# zx81_SD_09.net
KiCad netlist of a schematic drawn in EAGLE
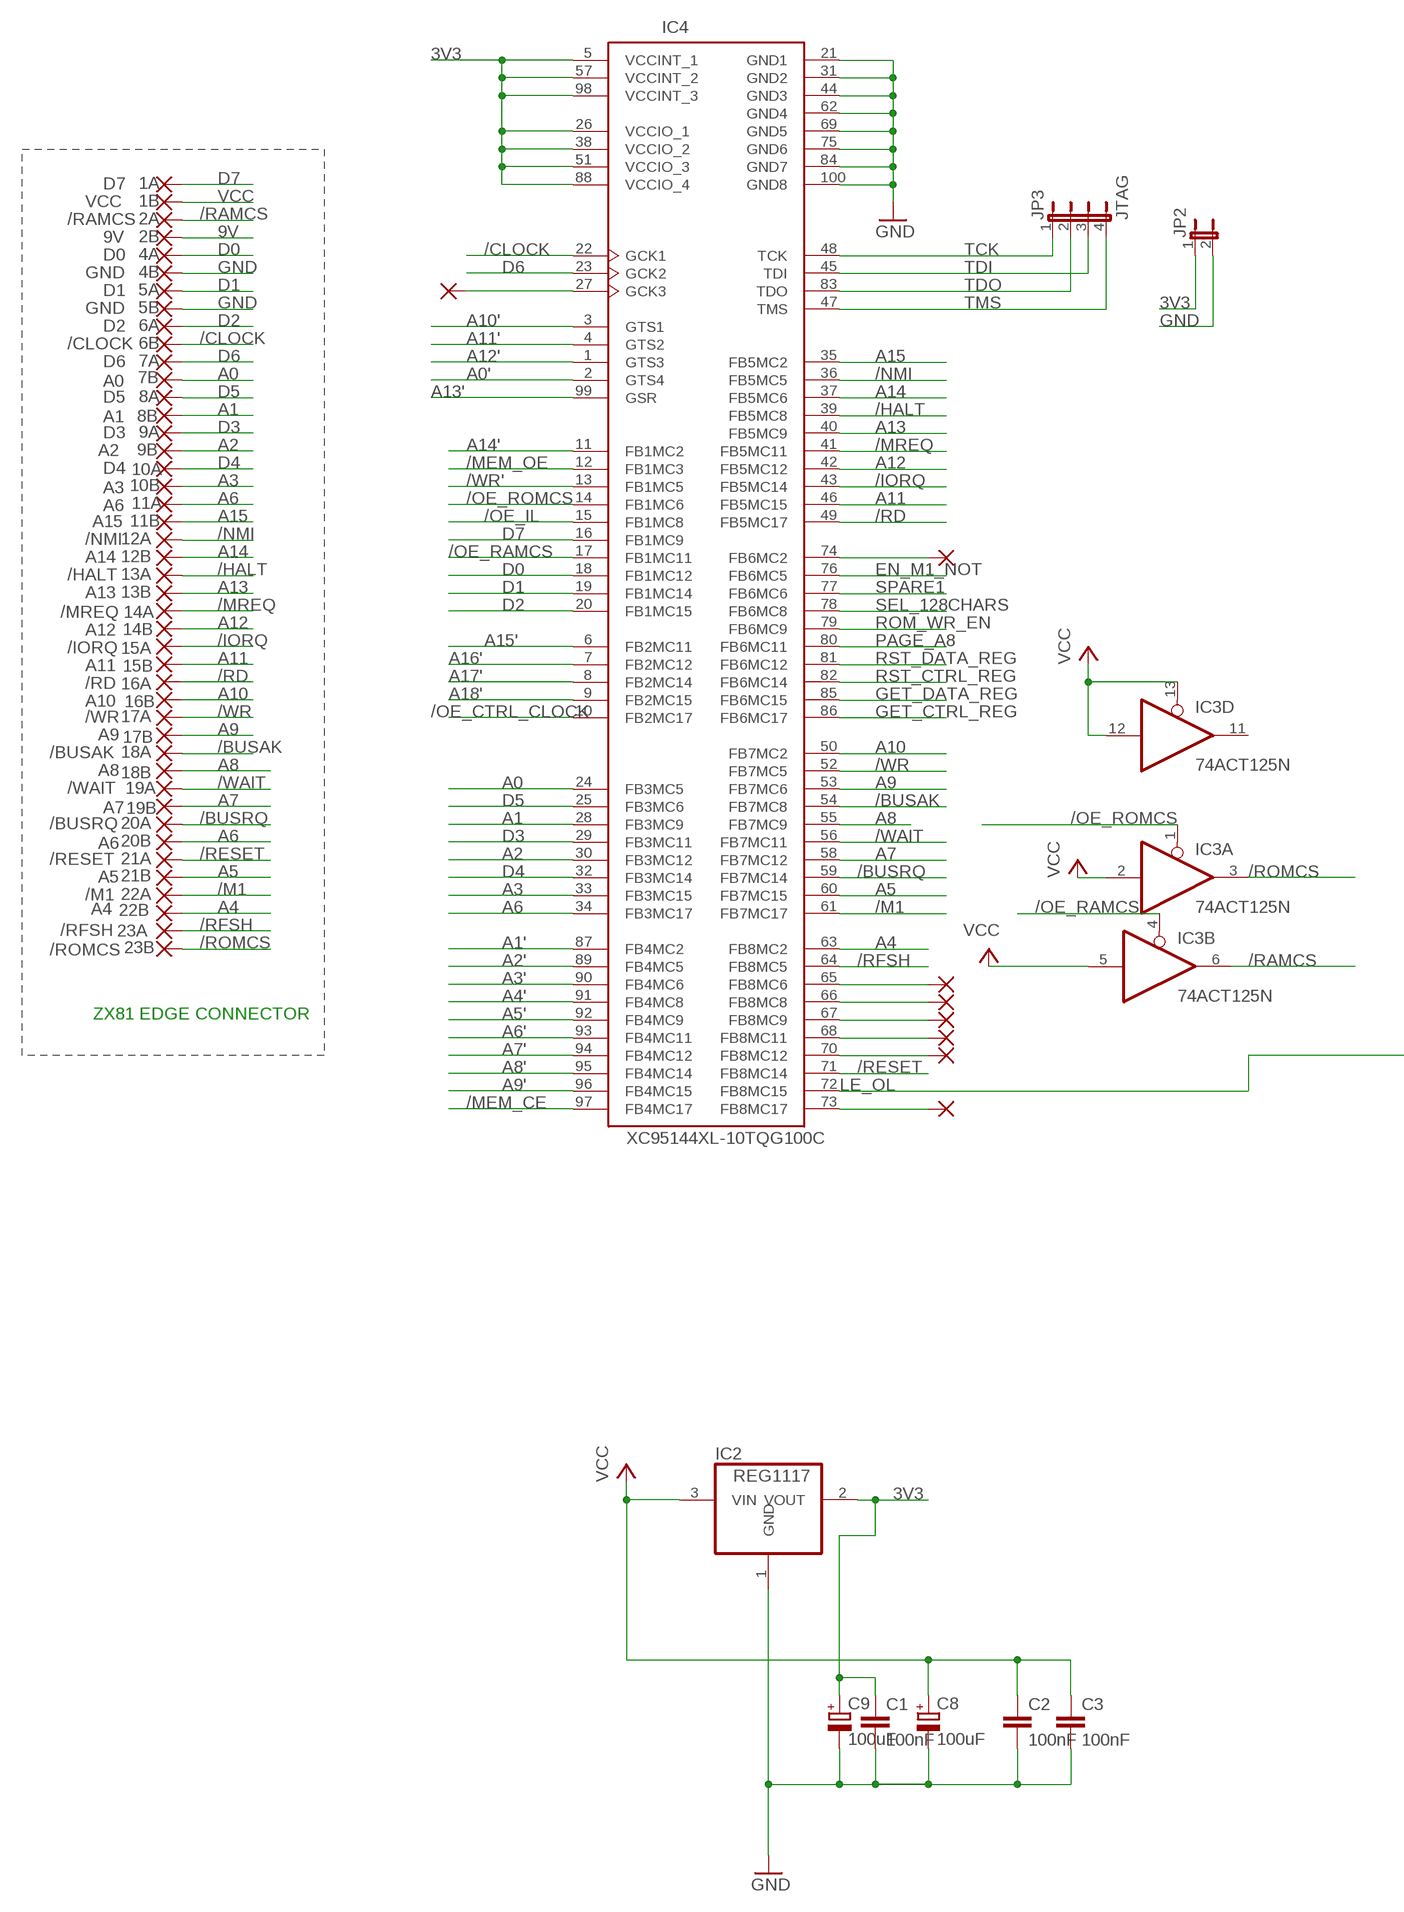
[diagram p0: schematic, sheet 1, part 1 of 2]
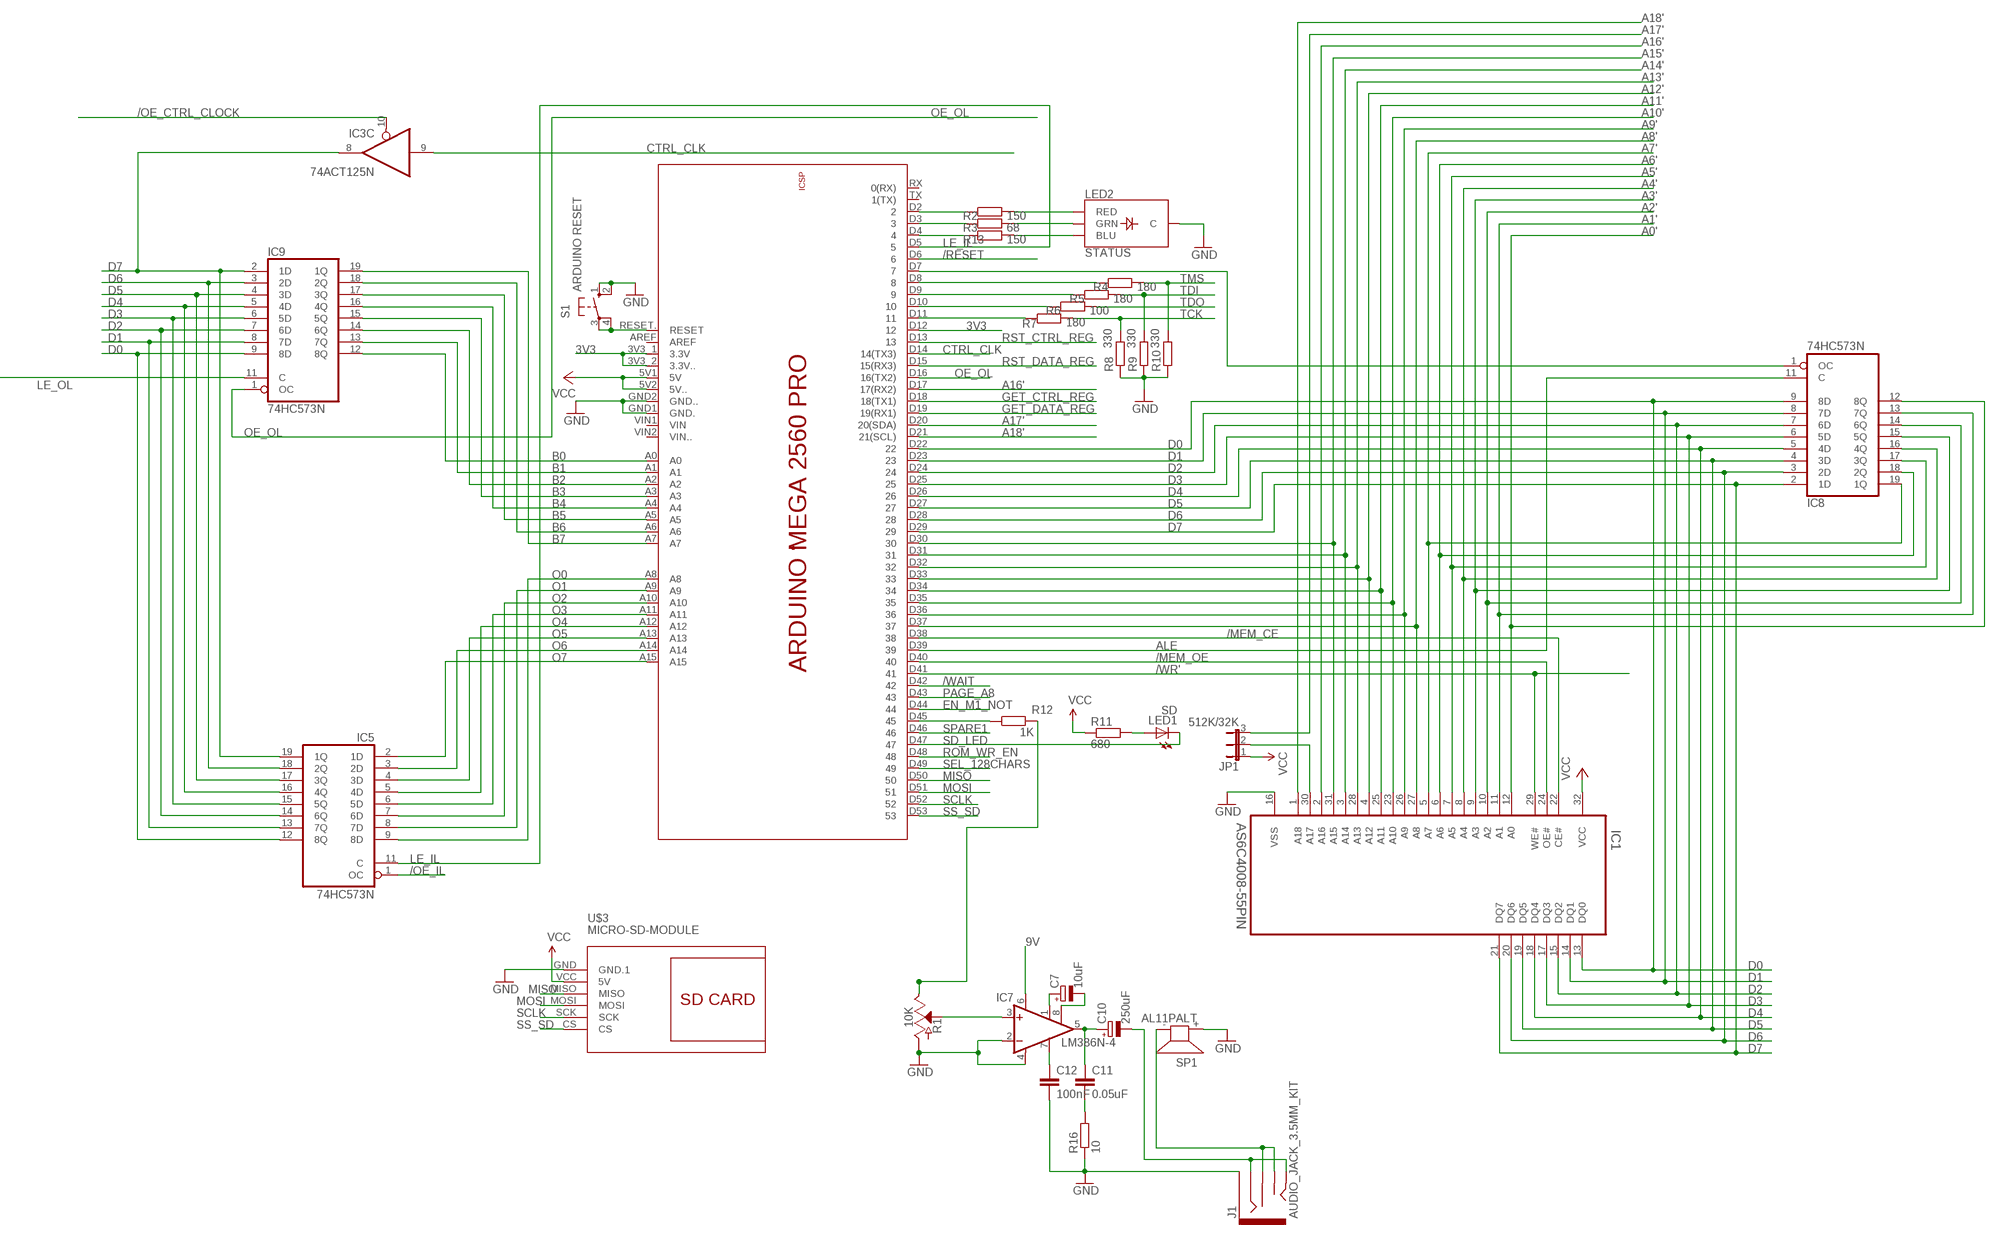
[diagram p1: schematic, sheet 1, part 2 of 2]

(export (version "E")
  (design (tool "Eeschema 10.0.6"))
  (components
    (comp (ref "1A")
      (value "D7")
      (footprint "eagle-import:EDGEPIN")
      (libsource (lib "eagle-import") (part "SMD2EDGEPIN"))
    )
    (comp (ref "1B")
      (value "VCC")
      (footprint "eagle-import:EDGEPIN")
      (libsource (lib "eagle-import") (part "SMD2EDGEPIN"))
    )
    (comp (ref "2A")
      (value "/RAMCS")
      (footprint "eagle-import:EDGEPIN")
      (libsource (lib "eagle-import") (part "SMD2EDGEPIN"))
    )
    (comp (ref "2B")
      (value "9V")
      (footprint "eagle-import:EDGEPIN")
      (libsource (lib "eagle-import") (part "SMD2EDGEPIN"))
    )
    (comp (ref "4A")
      (value "D0")
      (footprint "eagle-import:EDGEPIN")
      (libsource (lib "eagle-import") (part "SMD2EDGEPIN"))
    )
    (comp (ref "4B")
      (value "GND")
      (footprint "eagle-import:EDGEPIN")
      (libsource (lib "eagle-import") (part "SMD2EDGEPIN"))
    )
    (comp (ref "5A")
      (value "D1")
      (footprint "eagle-import:EDGEPIN")
      (libsource (lib "eagle-import") (part "SMD2EDGEPIN"))
    )
    (comp (ref "5B")
      (value "GND")
      (footprint "eagle-import:EDGEPIN")
      (libsource (lib "eagle-import") (part "SMD2EDGEPIN"))
    )
    (comp (ref "6A")
      (value "D2")
      (footprint "eagle-import:EDGEPIN")
      (libsource (lib "eagle-import") (part "SMD2EDGEPIN"))
    )
    (comp (ref "6B")
      (value "/CLOCK")
      (footprint "eagle-import:EDGEPIN")
      (libsource (lib "eagle-import") (part "SMD2EDGEPIN"))
    )
    (comp (ref "7A")
      (value "D6")
      (footprint "eagle-import:EDGEPIN")
      (libsource (lib "eagle-import") (part "SMD2EDGEPIN"))
    )
    (comp (ref "7B")
      (value "A0")
      (footprint "eagle-import:EDGEPIN")
      (libsource (lib "eagle-import") (part "SMD2EDGEPIN"))
    )
    (comp (ref "8A")
      (value "D5")
      (footprint "eagle-import:EDGEPIN")
      (libsource (lib "eagle-import") (part "SMD2EDGEPIN"))
    )
    (comp (ref "8B")
      (value "A1")
      (footprint "eagle-import:EDGEPIN")
      (libsource (lib "eagle-import") (part "SMD2EDGEPIN"))
    )
    (comp (ref "9A")
      (value "D3")
      (footprint "eagle-import:EDGEPIN")
      (libsource (lib "eagle-import") (part "SMD2EDGEPIN"))
    )
    (comp (ref "9B")
      (value "A2")
      (footprint "eagle-import:EDGEPIN")
      (libsource (lib "eagle-import") (part "SMD2EDGEPIN"))
    )
    (comp (ref "10A")
      (value "D4")
      (footprint "eagle-import:EDGEPIN")
      (libsource (lib "eagle-import") (part "SMD2EDGEPIN"))
    )
    (comp (ref "10B")
      (value "A3")
      (footprint "eagle-import:EDGEPIN")
      (libsource (lib "eagle-import") (part "SMD2EDGEPIN"))
    )
    (comp (ref "11A")
      (value "A6")
      (footprint "eagle-import:EDGEPIN")
      (libsource (lib "eagle-import") (part "SMD2EDGEPIN"))
    )
    (comp (ref "11B")
      (value "A15")
      (footprint "eagle-import:EDGEPIN")
      (libsource (lib "eagle-import") (part "SMD2EDGEPIN"))
    )
    (comp (ref "12A")
      (value "/NMI")
      (footprint "eagle-import:EDGEPIN")
      (libsource (lib "eagle-import") (part "SMD2EDGEPIN"))
    )
    (comp (ref "12B")
      (value "A14")
      (footprint "eagle-import:EDGEPIN")
      (libsource (lib "eagle-import") (part "SMD2EDGEPIN"))
    )
    (comp (ref "13A")
      (value "/HALT")
      (footprint "eagle-import:EDGEPIN")
      (libsource (lib "eagle-import") (part "SMD2EDGEPIN"))
    )
    (comp (ref "13B")
      (value "A13")
      (footprint "eagle-import:EDGEPIN")
      (libsource (lib "eagle-import") (part "SMD2EDGEPIN"))
    )
    (comp (ref "14A")
      (value "/MREQ")
      (footprint "eagle-import:EDGEPIN")
      (libsource (lib "eagle-import") (part "SMD2EDGEPIN"))
    )
    (comp (ref "14B")
      (value "A12")
      (footprint "eagle-import:EDGEPIN")
      (libsource (lib "eagle-import") (part "SMD2EDGEPIN"))
    )
    (comp (ref "15A")
      (value "/IORQ")
      (footprint "eagle-import:EDGEPIN")
      (libsource (lib "eagle-import") (part "SMD2EDGEPIN"))
    )
    (comp (ref "15B")
      (value "A11")
      (footprint "eagle-import:EDGEPIN")
      (libsource (lib "eagle-import") (part "SMD2EDGEPIN"))
    )
    (comp (ref "16A")
      (value "/RD")
      (footprint "eagle-import:EDGEPIN")
      (libsource (lib "eagle-import") (part "SMD2EDGEPIN"))
    )
    (comp (ref "16B")
      (value "A10")
      (footprint "eagle-import:EDGEPIN")
      (libsource (lib "eagle-import") (part "SMD2EDGEPIN"))
    )
    (comp (ref "17A")
      (value "/WR")
      (footprint "eagle-import:EDGEPIN")
      (libsource (lib "eagle-import") (part "SMD2EDGEPIN"))
    )
    (comp (ref "17B")
      (value "A9")
      (footprint "eagle-import:EDGEPIN")
      (libsource (lib "eagle-import") (part "SMD2EDGEPIN"))
    )
    (comp (ref "18A")
      (value "/BUSAK")
      (footprint "eagle-import:EDGEPIN")
      (libsource (lib "eagle-import") (part "SMD2EDGEPIN"))
    )
    (comp (ref "18B")
      (value "A8")
      (footprint "eagle-import:EDGEPIN")
      (libsource (lib "eagle-import") (part "SMD2EDGEPIN"))
    )
    (comp (ref "19A")
      (value "/WAIT")
      (footprint "eagle-import:EDGEPIN")
      (libsource (lib "eagle-import") (part "SMD2EDGEPIN"))
    )
    (comp (ref "19B")
      (value "A7")
      (footprint "eagle-import:EDGEPIN")
      (libsource (lib "eagle-import") (part "SMD2EDGEPIN"))
    )
    (comp (ref "20A")
      (value "/BUSRQ")
      (footprint "eagle-import:EDGEPIN")
      (libsource (lib "eagle-import") (part "SMD2EDGEPIN"))
    )
    (comp (ref "20B")
      (value "A6")
      (footprint "eagle-import:EDGEPIN")
      (libsource (lib "eagle-import") (part "SMD2EDGEPIN"))
    )
    (comp (ref "21A")
      (value "/RESET")
      (footprint "eagle-import:EDGEPIN")
      (libsource (lib "eagle-import") (part "SMD2EDGEPIN"))
    )
    (comp (ref "21B")
      (value "A5")
      (footprint "eagle-import:EDGEPIN")
      (libsource (lib "eagle-import") (part "SMD2EDGEPIN"))
    )
    (comp (ref "22A")
      (value "/M1")
      (footprint "eagle-import:EDGEPIN")
      (libsource (lib "eagle-import") (part "SMD2EDGEPIN"))
    )
    (comp (ref "22B")
      (value "A4")
      (footprint "eagle-import:EDGEPIN")
      (libsource (lib "eagle-import") (part "SMD2EDGEPIN"))
    )
    (comp (ref "23A")
      (value "/RFSH")
      (footprint "eagle-import:EDGEPIN")
      (libsource (lib "eagle-import") (part "SMD2EDGEPIN"))
    )
    (comp (ref "23B")
      (value "/ROMCS")
      (footprint "eagle-import:EDGEPIN")
      (libsource (lib "eagle-import") (part "SMD2EDGEPIN"))
    )
    (comp (ref "C1")
      (value "100nF")
      (footprint "eagle-import:C025-040X050")
      (libsource (lib "eagle-import") (part "C-EU025-040X050"))
    )
    (comp (ref "C2")
      (value "100nF")
      (footprint "eagle-import:C025-040X050")
      (libsource (lib "eagle-import") (part "C-EU025-040X050"))
    )
    (comp (ref "C3")
      (value "100nF")
      (footprint "eagle-import:C025-040X050")
      (libsource (lib "eagle-import") (part "C-EU025-040X050"))
    )
    (comp (ref "C7")
      (value "10uF")
      (footprint "eagle-import:E2-5")
      (libsource (lib "eagle-import") (part "CPOL-EUE2-5"))
    )
    (comp (ref "C8")
      (value "100uF")
      (footprint "eagle-import:E2-5")
      (libsource (lib "eagle-import") (part "CPOL-EUE2-5"))
    )
    (comp (ref "C9")
      (value "100uF")
      (footprint "eagle-import:E2-5")
      (libsource (lib "eagle-import") (part "CPOL-EUE2-5"))
    )
    (comp (ref "C10")
      (value "250uF")
      (footprint "eagle-import:E2-5")
      (libsource (lib "eagle-import") (part "CPOL-EUE2-5"))
    )
    (comp (ref "C11")
      (value "0.05uF")
      (footprint "eagle-import:C025-040X050")
      (libsource (lib "eagle-import") (part "C-EU025-040X050"))
    )
    (comp (ref "C12")
      (value "100nF")
      (footprint "eagle-import:C025-040X050")
      (libsource (lib "eagle-import") (part "C-EU025-040X050"))
    )
    (comp (ref "IC1")
      (value "AS6C4008-55PIN")
      (footprint "eagle-import:DIP1524W45P254L4203H406Q32")
      (fields (field (name "MF") "Alliance"))
      (libsource (lib "eagle-import") (part "AS6C4008-55PIN"))
    )
    (comp (ref "IC2")
      (value "REG1117")
      (footprint "eagle-import:SOT223")
      (libsource (lib "eagle-import") (part "REG1117"))
    )
    (comp (ref "IC3")
      (value "74ACT125N")
      (footprint "eagle-import:DIL14")
      (libsource (lib "eagle-import") (part "74125NACT"))
    )
    (comp (ref "IC4")
      (value "XC95144XL-10TQG100C")
      (footprint "eagle-import:TQFP100")
      (fields (field (name "MF") "Xilinx Inc."))
      (libsource (lib "eagle-import") (part "XC95144XL-10TQG100C"))
    )
    (comp (ref "IC5")
      (value "74HC573N")
      (footprint "eagle-import:DIL20")
      (libsource (lib "eagle-import") (part "74573NHC"))
    )
    (comp (ref "IC7")
      (value "LM386N-4")
      (footprint "eagle-import:DIL08")
      (libsource (lib "eagle-import") (part "LM386?-N4"))
    )
    (comp (ref "IC8")
      (value "74HC573N")
      (footprint "eagle-import:DIL20")
      (libsource (lib "eagle-import") (part "74573NHC"))
    )
    (comp (ref "IC9")
      (value "74HC573N")
      (footprint "eagle-import:DIL20")
      (libsource (lib "eagle-import") (part "74573NHC"))
    )
    (comp (ref "J1")
      (value "AUDIO_JACK_3.5MM_KIT")
      (footprint "eagle-import:AUDIO-JACK-KIT")
      (libsource (lib "eagle-import") (part "AUDIO_JACK_3.5MM_KIT"))
    )
    (comp (ref "JP1")
      (value "512K/32K")
      (footprint "eagle-import:JP2")
      (libsource (lib "eagle-import") (part "JP2E"))
    )
    (comp (ref "JP2")
      (value "JP1E")
      (footprint "eagle-import:JP1")
      (libsource (lib "eagle-import") (part "JP1E"))
    )
    (comp (ref "JP3")
      (value "JTAG")
      (footprint "eagle-import:JP4")
      (libsource (lib "eagle-import") (part "JP4E"))
    )
    (comp (ref "LED1")
      (value "SD")
      (footprint "eagle-import:LED5MM")
      (libsource (lib "eagle-import") (part "LED5MM"))
    )
    (comp (ref "LED2")
      (value "STATUS")
      (footprint "eagle-import:LED-RGB-THRU")
      (libsource (lib "eagle-import") (part "LED-RGB-CCDIFFUSE"))
    )
    (comp (ref "PAD1")
      (value "1,6/0,8")
      (footprint "eagle-import:1,6_0,8")
      (libsource (lib "eagle-import") (part "1,6/0,8"))
    )
    (comp (ref "PAD2")
      (value "1,6/0,8")
      (footprint "eagle-import:1,6_0,8")
      (libsource (lib "eagle-import") (part "1,6/0,8"))
    )
    (comp (ref "PAD3")
      (value "1,6/0,8")
      (footprint "eagle-import:1,6_0,8")
      (libsource (lib "eagle-import") (part "1,6/0,8"))
    )
    (comp (ref "PAD4")
      (value "1,6/0,8")
      (footprint "eagle-import:1,6_0,8")
      (libsource (lib "eagle-import") (part "1,6/0,8"))
    )
    (comp (ref "PAD5")
      (value "1,6/0,8")
      (footprint "eagle-import:1,6_0,8")
      (libsource (lib "eagle-import") (part "1,6/0,8"))
    )
    (comp (ref "PAD6")
      (value "1,6/0,8")
      (footprint "eagle-import:1,6_0,8")
      (libsource (lib "eagle-import") (part "1,6/0,8"))
    )
    (comp (ref "PAD7")
      (value "1,6/0,8")
      (footprint "eagle-import:1,6_0,8")
      (libsource (lib "eagle-import") (part "1,6/0,8"))
    )
    (comp (ref "PAD8")
      (value "1,6/0,8")
      (footprint "eagle-import:1,6_0,8")
      (libsource (lib "eagle-import") (part "1,6/0,8"))
    )
    (comp (ref "R1")
      (value "10K")
      (footprint "eagle-import:POT-WHEEL")
      (libsource (lib "eagle-import") (part "POT"))
    )
    (comp (ref "R2")
      (value "150")
      (footprint "eagle-import:0204_7")
      (libsource (lib "eagle-import") (part "rcl_334_R-EU_0204/7"))
    )
    (comp (ref "R3")
      (value "68")
      (footprint "eagle-import:0204_7")
      (libsource (lib "eagle-import") (part "rcl_334_R-EU_0204/7"))
    )
    (comp (ref "R4")
      (value "180")
      (footprint "eagle-import:0204_7")
      (libsource (lib "eagle-import") (part "rcl_334_R-EU_0204/7"))
    )
    (comp (ref "R5")
      (value "180")
      (footprint "eagle-import:0204_7")
      (libsource (lib "eagle-import") (part "rcl_334_R-EU_0204/7"))
    )
    (comp (ref "R6")
      (value "100")
      (footprint "eagle-import:0204_7")
      (libsource (lib "eagle-import") (part "rcl_334_R-EU_0204/7"))
    )
    (comp (ref "R7")
      (value "180")
      (footprint "eagle-import:0204_7")
      (libsource (lib "eagle-import") (part "rcl_334_R-EU_0204/7"))
    )
    (comp (ref "R8")
      (value "330")
      (footprint "eagle-import:0204_7")
      (libsource (lib "eagle-import") (part "rcl_334_R-EU_0204/7"))
    )
    (comp (ref "R9")
      (value "330")
      (footprint "eagle-import:0204_7")
      (libsource (lib "eagle-import") (part "rcl_334_R-EU_0204/7"))
    )
    (comp (ref "R10")
      (value "330")
      (footprint "eagle-import:0204_7")
      (libsource (lib "eagle-import") (part "rcl_334_R-EU_0204/7"))
    )
    (comp (ref "R11")
      (value "680")
      (footprint "eagle-import:0204_7")
      (libsource (lib "eagle-import") (part "R-EU_0204/7"))
    )
    (comp (ref "R12")
      (value "1K")
      (footprint "eagle-import:0204_7")
      (libsource (lib "eagle-import") (part "R-EU_0204/7"))
    )
    (comp (ref "R13")
      (value "150")
      (footprint "eagle-import:0204_7")
      (libsource (lib "eagle-import") (part "rcl_334_R-EU_0204/7"))
    )
    (comp (ref "R16")
      (value "10")
      (footprint "eagle-import:0204_7")
      (libsource (lib "eagle-import") (part "R-EU_0204/7"))
    )
    (comp (ref "S1")
      (value "ARDUINO RESET")
      (footprint "eagle-import:B3F-10XX")
      (fields (field (name "MPN") "B3F-1000"))
      (libsource (lib "eagle-import") (part "10-XX"))
    )
    (comp (ref "SP1")
      (value "AL11PALT")
      (footprint "eagle-import:ALT")
      (libsource (lib "eagle-import") (part "AL11PALT"))
    )
    (comp (ref "U$2")
      (value "ARDUINO_MEGA2560_PRO")
      (footprint "eagle-import:ARDUINO_MEGA2560_PRO")
      (libsource (lib "eagle-import") (part "ARDUINO_MEGA2560_PRO"))
    )
    (comp (ref "U$3")
      (value "MICRO-SD-MODULE")
      (footprint "eagle-import:MICROSD-MODULE")
      (libsource (lib "eagle-import") (part "MICRO-SD-MODULE"))
    )
  )
  (nets
    (net (code "1") (name "/3V3") (class "Default")
      (node (ref "C1") (pin "1") (pinfunction "1_1") (pintype "passive"))
      (node (ref "C9") (pin "+") (pinfunction "+_+") (pintype "passive"))
      (node (ref "IC2") (pin "2") (pinfunction "VOUT_2") (pintype "output"))
      (node (ref "IC4") (pin "26") (pinfunction "VCCIO_1_26") (pintype "power_in"))
      (node (ref "IC4") (pin "38") (pinfunction "VCCIO_2_38") (pintype "power_in"))
      (node (ref "IC4") (pin "5") (pinfunction "VCCINT_1_5") (pintype "power_in"))
      (node (ref "IC4") (pin "51") (pinfunction "VCCIO_3_51") (pintype "power_in"))
      (node (ref "IC4") (pin "57") (pinfunction "VCCINT_2_57") (pintype "power_in"))
      (node (ref "IC4") (pin "88") (pinfunction "VCCIO_4_88") (pintype "power_in"))
      (node (ref "IC4") (pin "98") (pinfunction "VCCINT_3_98") (pintype "power_in"))
      (node (ref "JP2") (pin "1") (pinfunction "1_1") (pintype "passive"))
      (node (ref "U$2") (pin "3V3_1") (pinfunction "3.3V_3V3_1") (pintype "bidirectional"))
      (node (ref "U$2") (pin "3V3_2") (pinfunction "3.3V.._3V3_2") (pintype "bidirectional"))
      (node (ref "U$2") (pin "D12") (pinfunction "12_D12") (pintype "bidirectional"))
    )
    (net (code "2") (name "/9V") (class "Default")
      (node (ref "2B") (pin "1") (pinfunction "P_1") (pintype "passive"))
      (node (ref "IC7") (pin "6") (pinfunction "VS_6") (pintype "power_in"))
    )
    (net (code "3") (name "/A0") (class "Default")
      (node (ref "7B") (pin "1") (pinfunction "P_1") (pintype "passive"))
      (node (ref "IC4") (pin "24") (pinfunction "FB3MC5_24") (pintype "bidirectional"))
    )
    (net (code "4") (name "/A0'") (class "Default")
      (node (ref "IC1") (pin "12") (pinfunction "A0_12") (pintype "input"))
      (node (ref "IC4") (pin "2") (pinfunction "GTS4_2") (pintype "bidirectional"))
      (node (ref "IC8") (pin "12") (pinfunction "8Q_12") (pintype "tri_state"))
    )
    (net (code "5") (name "/A1") (class "Default")
      (node (ref "8B") (pin "1") (pinfunction "P_1") (pintype "passive"))
      (node (ref "IC4") (pin "28") (pinfunction "FB3MC9_28") (pintype "bidirectional"))
    )
    (net (code "6") (name "/A1'") (class "Default")
      (node (ref "IC1") (pin "11") (pinfunction "A1_11") (pintype "input"))
      (node (ref "IC4") (pin "87") (pinfunction "FB4MC2_87") (pintype "bidirectional"))
      (node (ref "IC8") (pin "13") (pinfunction "7Q_13") (pintype "tri_state"))
    )
    (net (code "7") (name "/A2") (class "Default")
      (node (ref "9B") (pin "1") (pinfunction "P_1") (pintype "passive"))
      (node (ref "IC4") (pin "30") (pinfunction "FB3MC12_30") (pintype "bidirectional"))
    )
    (net (code "8") (name "/A2'") (class "Default")
      (node (ref "IC1") (pin "10") (pinfunction "A2_10") (pintype "input"))
      (node (ref "IC4") (pin "89") (pinfunction "FB4MC5_89") (pintype "bidirectional"))
      (node (ref "IC8") (pin "14") (pinfunction "6Q_14") (pintype "tri_state"))
    )
    (net (code "9") (name "/A3") (class "Default")
      (node (ref "10B") (pin "1") (pinfunction "P_1") (pintype "passive"))
      (node (ref "IC4") (pin "33") (pinfunction "FB3MC15_33") (pintype "bidirectional"))
    )
    (net (code "10") (name "/A3'") (class "Default")
      (node (ref "IC1") (pin "9") (pinfunction "A3_9") (pintype "input"))
      (node (ref "IC4") (pin "90") (pinfunction "FB4MC6_90") (pintype "bidirectional"))
      (node (ref "IC8") (pin "15") (pinfunction "5Q_15") (pintype "tri_state"))
    )
    (net (code "11") (name "/A4") (class "Default")
      (node (ref "22B") (pin "1") (pinfunction "P_1") (pintype "passive"))
      (node (ref "IC4") (pin "63") (pinfunction "FB8MC2_63") (pintype "bidirectional"))
    )
    (net (code "12") (name "/A4'") (class "Default")
      (node (ref "IC1") (pin "8") (pinfunction "A4_8") (pintype "input"))
      (node (ref "IC4") (pin "91") (pinfunction "FB4MC8_91") (pintype "bidirectional"))
      (node (ref "IC8") (pin "16") (pinfunction "4Q_16") (pintype "tri_state"))
    )
    (net (code "13") (name "/A5") (class "Default")
      (node (ref "21B") (pin "1") (pinfunction "P_1") (pintype "passive"))
      (node (ref "IC4") (pin "60") (pinfunction "FB7MC15_60") (pintype "bidirectional"))
    )
    (net (code "14") (name "/A5'") (class "Default")
      (node (ref "IC1") (pin "7") (pinfunction "A5_7") (pintype "input"))
      (node (ref "IC4") (pin "92") (pinfunction "FB4MC9_92") (pintype "bidirectional"))
      (node (ref "IC8") (pin "17") (pinfunction "3Q_17") (pintype "tri_state"))
    )
    (net (code "15") (name "/A6") (class "Default")
      (node (ref "11A") (pin "1") (pinfunction "P_1") (pintype "passive"))
      (node (ref "20B") (pin "1") (pinfunction "P_1") (pintype "passive"))
      (node (ref "IC4") (pin "34") (pinfunction "FB3MC17_34") (pintype "bidirectional"))
    )
    (net (code "16") (name "/A6'") (class "Default")
      (node (ref "IC1") (pin "6") (pinfunction "A6_6") (pintype "input"))
      (node (ref "IC4") (pin "93") (pinfunction "FB4MC11_93") (pintype "bidirectional"))
      (node (ref "IC8") (pin "18") (pinfunction "2Q_18") (pintype "tri_state"))
    )
    (net (code "17") (name "/A7") (class "Default")
      (node (ref "19B") (pin "1") (pinfunction "P_1") (pintype "passive"))
      (node (ref "IC4") (pin "58") (pinfunction "FB7MC12_58") (pintype "bidirectional"))
    )
    (net (code "18") (name "/A7'") (class "Default")
      (node (ref "IC1") (pin "5") (pinfunction "A7_5") (pintype "input"))
      (node (ref "IC4") (pin "94") (pinfunction "FB4MC12_94") (pintype "bidirectional"))
      (node (ref "IC8") (pin "19") (pinfunction "1Q_19") (pintype "tri_state"))
    )
    (net (code "19") (name "/A8") (class "Default")
      (node (ref "18B") (pin "1") (pinfunction "P_1") (pintype "passive"))
      (node (ref "IC4") (pin "55") (pinfunction "FB7MC9_55") (pintype "bidirectional"))
    )
    (net (code "20") (name "/A8'") (class "Default")
      (node (ref "IC1") (pin "27") (pinfunction "A8_27") (pintype "input"))
      (node (ref "IC4") (pin "95") (pinfunction "FB4MC14_95") (pintype "bidirectional"))
      (node (ref "U$2") (pin "D37") (pinfunction "37_D37") (pintype "bidirectional"))
    )
    (net (code "21") (name "/A9") (class "Default")
      (node (ref "17B") (pin "1") (pinfunction "P_1") (pintype "passive"))
      (node (ref "IC4") (pin "53") (pinfunction "FB7MC6_53") (pintype "bidirectional"))
    )
    (net (code "22") (name "/A9'") (class "Default")
      (node (ref "IC1") (pin "26") (pinfunction "A9_26") (pintype "input"))
      (node (ref "IC4") (pin "96") (pinfunction "FB4MC15_96") (pintype "bidirectional"))
      (node (ref "U$2") (pin "D36") (pinfunction "36_D36") (pintype "bidirectional"))
    )
    (net (code "23") (name "/A10") (class "Default")
      (node (ref "16B") (pin "1") (pinfunction "P_1") (pintype "passive"))
      (node (ref "IC4") (pin "50") (pinfunction "FB7MC2_50") (pintype "bidirectional"))
    )
    (net (code "24") (name "/A10'") (class "Default")
      (node (ref "IC1") (pin "23") (pinfunction "A10_23") (pintype "input"))
      (node (ref "IC4") (pin "3") (pinfunction "GTS1_3") (pintype "bidirectional"))
      (node (ref "U$2") (pin "D35") (pinfunction "35_D35") (pintype "bidirectional"))
    )
    (net (code "25") (name "/A11") (class "Default")
      (node (ref "15B") (pin "1") (pinfunction "P_1") (pintype "passive"))
      (node (ref "IC4") (pin "46") (pinfunction "FB5MC15_46") (pintype "bidirectional"))
    )
    (net (code "26") (name "/A11'") (class "Default")
      (node (ref "IC1") (pin "25") (pinfunction "A11_25") (pintype "input"))
      (node (ref "IC4") (pin "4") (pinfunction "GTS2_4") (pintype "bidirectional"))
      (node (ref "U$2") (pin "D34") (pinfunction "34_D34") (pintype "bidirectional"))
    )
    (net (code "27") (name "/A12") (class "Default")
      (node (ref "14B") (pin "1") (pinfunction "P_1") (pintype "passive"))
      (node (ref "IC4") (pin "42") (pinfunction "FB5MC12_42") (pintype "bidirectional"))
    )
    (net (code "28") (name "/A12'") (class "Default")
      (node (ref "IC1") (pin "4") (pinfunction "A12_4") (pintype "input"))
      (node (ref "IC4") (pin "1") (pinfunction "GTS3_1") (pintype "bidirectional"))
      (node (ref "U$2") (pin "D33") (pinfunction "33_D33") (pintype "bidirectional"))
    )
    (net (code "29") (name "/A13") (class "Default")
      (node (ref "13B") (pin "1") (pinfunction "P_1") (pintype "passive"))
      (node (ref "IC4") (pin "40") (pinfunction "FB5MC9_40") (pintype "bidirectional"))
    )
    (net (code "30") (name "/A13'") (class "Default")
      (node (ref "IC1") (pin "28") (pinfunction "A13_28") (pintype "input"))
      (node (ref "IC4") (pin "99") (pinfunction "GSR_99") (pintype "bidirectional"))
      (node (ref "U$2") (pin "D32") (pinfunction "32_D32") (pintype "bidirectional"))
    )
    (net (code "31") (name "/A14") (class "Default")
      (node (ref "12B") (pin "1") (pinfunction "P_1") (pintype "passive"))
      (node (ref "IC4") (pin "37") (pinfunction "FB5MC6_37") (pintype "bidirectional"))
    )
    (net (code "32") (name "/A14'") (class "Default")
      (node (ref "IC1") (pin "3") (pinfunction "A14_3") (pintype "input"))
      (node (ref "IC4") (pin "11") (pinfunction "FB1MC2_11") (pintype "bidirectional"))
      (node (ref "U$2") (pin "D31") (pinfunction "31_D31") (pintype "bidirectional"))
    )
    (net (code "33") (name "/A15") (class "Default")
      (node (ref "11B") (pin "1") (pinfunction "P_1") (pintype "passive"))
      (node (ref "IC4") (pin "35") (pinfunction "FB5MC2_35") (pintype "bidirectional"))
    )
    (net (code "34") (name "/A15'") (class "Default")
      (node (ref "IC1") (pin "31") (pinfunction "A15_31") (pintype "input"))
      (node (ref "IC4") (pin "6") (pinfunction "FB2MC11_6") (pintype "bidirectional"))
      (node (ref "U$2") (pin "D30") (pinfunction "30_D30") (pintype "bidirectional"))
    )
    (net (code "35") (name "/A16'") (class "Default")
      (node (ref "IC1") (pin "2") (pinfunction "A16_2") (pintype "input"))
      (node (ref "IC4") (pin "7") (pinfunction "FB2MC12_7") (pintype "bidirectional"))
      (node (ref "U$2") (pin "D17") (pinfunction "17(RX2)_D17") (pintype "bidirectional"))
    )
    (net (code "36") (name "/A17'") (class "Default")
      (node (ref "IC4") (pin "8") (pinfunction "FB2MC14_8") (pintype "bidirectional"))
      (node (ref "JP1") (pin "3") (pinfunction "3_3") (pintype "passive"))
      (node (ref "U$2") (pin "D20") (pinfunction "20(SDA)_D20") (pintype "bidirectional"))
    )
    (net (code "37") (name "/A18'") (class "Default")
      (node (ref "IC1") (pin "1") (pinfunction "A18_1") (pintype "input"))
      (node (ref "IC4") (pin "9") (pinfunction "FB2MC15_9") (pintype "bidirectional"))
      (node (ref "U$2") (pin "D21") (pinfunction "21(SCL)_D21") (pintype "bidirectional"))
    )
    (net (code "38") (name "/ALE") (class "Default")
      (node (ref "IC8") (pin "11") (pinfunction "C_11") (pintype "input"))
      (node (ref "U$2") (pin "D39") (pinfunction "39_D39") (pintype "bidirectional"))
    )
    (net (code "39") (name "/B0") (class "Default")
      (node (ref "IC9") (pin "19") (pinfunction "1Q_19") (pintype "tri_state"))
      (node (ref "U$2") (pin "A7") (pinfunction "A7_A7") (pintype "bidirectional"))
    )
    (net (code "40") (name "/B1") (class "Default")
      (node (ref "IC9") (pin "18") (pinfunction "2Q_18") (pintype "tri_state"))
      (node (ref "U$2") (pin "A6") (pinfunction "A6_A6") (pintype "bidirectional"))
    )
    (net (code "41") (name "/B2") (class "Default")
      (node (ref "IC9") (pin "17") (pinfunction "3Q_17") (pintype "tri_state"))
      (node (ref "U$2") (pin "A5") (pinfunction "A5_A5") (pintype "bidirectional"))
    )
    (net (code "42") (name "/B3") (class "Default")
      (node (ref "IC9") (pin "16") (pinfunction "4Q_16") (pintype "tri_state"))
      (node (ref "U$2") (pin "A4") (pinfunction "A4_A4") (pintype "bidirectional"))
    )
    (net (code "43") (name "/B4") (class "Default")
      (node (ref "IC9") (pin "15") (pinfunction "5Q_15") (pintype "tri_state"))
      (node (ref "U$2") (pin "A3") (pinfunction "A3_A3") (pintype "bidirectional"))
    )
    (net (code "44") (name "/B5") (class "Default")
      (node (ref "IC9") (pin "14") (pinfunction "6Q_14") (pintype "tri_state"))
      (node (ref "U$2") (pin "A2") (pinfunction "A2_A2") (pintype "bidirectional"))
    )
    (net (code "45") (name "/B6") (class "Default")
      (node (ref "IC9") (pin "13") (pinfunction "7Q_13") (pintype "tri_state"))
      (node (ref "U$2") (pin "A1") (pinfunction "A1_A1") (pintype "bidirectional"))
    )
    (net (code "46") (name "/B7") (class "Default")
      (node (ref "IC9") (pin "12") (pinfunction "8Q_12") (pintype "tri_state"))
      (node (ref "U$2") (pin "A0") (pinfunction "A0_A0") (pintype "bidirectional"))
    )
    (net (code "47") (name "/CTRL_CLK") (class "Default")
      (node (ref "IC3") (pin "9") (pinfunction "I_9") (pintype "input"))
      (node (ref "U$2") (pin "D14") (pinfunction "14(TX3)_D14") (pintype "bidirectional"))
    )
    (net (code "48") (name "/D0") (class "Default")
      (node (ref "4A") (pin "1") (pinfunction "P_1") (pintype "passive"))
      (node (ref "IC1") (pin "13") (pinfunction "DQ0_13") (pintype "bidirectional"))
      (node (ref "IC4") (pin "18") (pinfunction "FB1MC12_18") (pintype "bidirectional"))
      (node (ref "IC5") (pin "12") (pinfunction "8Q_12") (pintype "tri_state"))
      (node (ref "IC8") (pin "9") (pinfunction "8D_9") (pintype "input"))
      (node (ref "IC9") (pin "9") (pinfunction "8D_9") (pintype "input"))
      (node (ref "U$2") (pin "D22") (pinfunction "22_D22") (pintype "bidirectional"))
    )
    (net (code "49") (name "/D1") (class "Default")
      (node (ref "5A") (pin "1") (pinfunction "P_1") (pintype "passive"))
      (node (ref "IC1") (pin "14") (pinfunction "DQ1_14") (pintype "bidirectional"))
      (node (ref "IC4") (pin "19") (pinfunction "FB1MC14_19") (pintype "bidirectional"))
      (node (ref "IC5") (pin "13") (pinfunction "7Q_13") (pintype "tri_state"))
      (node (ref "IC8") (pin "8") (pinfunction "7D_8") (pintype "input"))
      (node (ref "IC9") (pin "8") (pinfunction "7D_8") (pintype "input"))
      (node (ref "U$2") (pin "D23") (pinfunction "23_D23") (pintype "bidirectional"))
    )
    (net (code "50") (name "/D2") (class "Default")
      (node (ref "6A") (pin "1") (pinfunction "P_1") (pintype "passive"))
      (node (ref "IC1") (pin "15") (pinfunction "DQ2_15") (pintype "bidirectional"))
      (node (ref "IC4") (pin "20") (pinfunction "FB1MC15_20") (pintype "bidirectional"))
      (node (ref "IC5") (pin "14") (pinfunction "6Q_14") (pintype "tri_state"))
      (node (ref "IC8") (pin "7") (pinfunction "6D_7") (pintype "input"))
      (node (ref "IC9") (pin "7") (pinfunction "6D_7") (pintype "input"))
      (node (ref "U$2") (pin "D24") (pinfunction "24_D24") (pintype "bidirectional"))
    )
    (net (code "51") (name "/D3") (class "Default")
      (node (ref "9A") (pin "1") (pinfunction "P_1") (pintype "passive"))
      (node (ref "IC1") (pin "17") (pinfunction "DQ3_17") (pintype "bidirectional"))
      (node (ref "IC4") (pin "29") (pinfunction "FB3MC11_29") (pintype "bidirectional"))
      (node (ref "IC5") (pin "15") (pinfunction "5Q_15") (pintype "tri_state"))
      (node (ref "IC8") (pin "6") (pinfunction "5D_6") (pintype "input"))
      (node (ref "IC9") (pin "6") (pinfunction "5D_6") (pintype "input"))
      (node (ref "U$2") (pin "D25") (pinfunction "25_D25") (pintype "bidirectional"))
    )
    (net (code "52") (name "/D4") (class "Default")
      (node (ref "10A") (pin "1") (pinfunction "P_1") (pintype "passive"))
      (node (ref "IC1") (pin "18") (pinfunction "DQ4_18") (pintype "bidirectional"))
      (node (ref "IC4") (pin "32") (pinfunction "FB3MC14_32") (pintype "bidirectional"))
      (node (ref "IC5") (pin "16") (pinfunction "4Q_16") (pintype "tri_state"))
      (node (ref "IC8") (pin "5") (pinfunction "4D_5") (pintype "input"))
      (node (ref "IC9") (pin "5") (pinfunction "4D_5") (pintype "input"))
      (node (ref "U$2") (pin "D26") (pinfunction "26_D26") (pintype "bidirectional"))
    )
    (net (code "53") (name "/D5") (class "Default")
      (node (ref "8A") (pin "1") (pinfunction "P_1") (pintype "passive"))
      (node (ref "IC1") (pin "19") (pinfunction "DQ5_19") (pintype "bidirectional"))
      (node (ref "IC4") (pin "25") (pinfunction "FB3MC6_25") (pintype "bidirectional"))
      (node (ref "IC5") (pin "17") (pinfunction "3Q_17") (pintype "tri_state"))
      (node (ref "IC8") (pin "4") (pinfunction "3D_4") (pintype "input"))
      (node (ref "IC9") (pin "4") (pinfunction "3D_4") (pintype "input"))
      (node (ref "U$2") (pin "D27") (pinfunction "27_D27") (pintype "bidirectional"))
    )
    (net (code "54") (name "/D6") (class "Default")
      (node (ref "7A") (pin "1") (pinfunction "P_1") (pintype "passive"))
      (node (ref "IC1") (pin "20") (pinfunction "DQ6_20") (pintype "bidirectional"))
      (node (ref "IC4") (pin "23") (pinfunction "GCK2_23") (pintype "bidirectional"))
      (node (ref "IC5") (pin "18") (pinfunction "2Q_18") (pintype "tri_state"))
      (node (ref "IC8") (pin "3") (pinfunction "2D_3") (pintype "input"))
      (node (ref "IC9") (pin "3") (pinfunction "2D_3") (pintype "input"))
      (node (ref "U$2") (pin "D28") (pinfunction "28_D28") (pintype "bidirectional"))
    )
    (net (code "55") (name "/D7") (class "Default")
      (node (ref "1A") (pin "1") (pinfunction "P_1") (pintype "passive"))
      (node (ref "IC1") (pin "21") (pinfunction "DQ7_21") (pintype "bidirectional"))
      (node (ref "IC3") (pin "8") (pinfunction "O_8") (pintype "tri_state"))
      (node (ref "IC4") (pin "16") (pinfunction "FB1MC9_16") (pintype "bidirectional"))
      (node (ref "IC5") (pin "19") (pinfunction "1Q_19") (pintype "tri_state"))
      (node (ref "IC8") (pin "2") (pinfunction "1D_2") (pintype "input"))
      (node (ref "IC9") (pin "2") (pinfunction "1D_2") (pintype "input"))
      (node (ref "U$2") (pin "D29") (pinfunction "29_D29") (pintype "bidirectional"))
    )
    (net (code "56") (name "/EN_M1_NOT") (class "Default")
      (node (ref "IC4") (pin "76") (pinfunction "FB6MC5_76") (pintype "bidirectional"))
      (node (ref "U$2") (pin "D44") (pinfunction "44_D44") (pintype "bidirectional"))
    )
    (net (code "57") (name "/GET_CTRL_REG") (class "Default")
      (node (ref "IC4") (pin "86") (pinfunction "FB6MC17_86") (pintype "bidirectional"))
      (node (ref "U$2") (pin "D18") (pinfunction "18(TX1)_D18") (pintype "bidirectional"))
    )
    (net (code "58") (name "/GET_DATA_REG") (class "Default")
      (node (ref "IC4") (pin "85") (pinfunction "FB6MC15_85") (pintype "bidirectional"))
      (node (ref "U$2") (pin "D19") (pinfunction "19(RX1)_D19") (pintype "bidirectional"))
    )
    (net (code "59") (name "/LE_IL") (class "Default")
      (node (ref "IC5") (pin "11") (pinfunction "C_11") (pintype "input"))
      (node (ref "U$2") (pin "D5") (pinfunction "5_D5") (pintype "bidirectional"))
    )
    (net (code "60") (name "/LE_OL") (class "Default")
      (node (ref "IC4") (pin "72") (pinfunction "FB8MC15_72") (pintype "bidirectional"))
      (node (ref "IC9") (pin "11") (pinfunction "C_11") (pintype "input"))
    )
    (net (code "61") (name "/MISO") (class "Default")
      (node (ref "U$2") (pin "D50") (pinfunction "50_D50") (pintype "bidirectional"))
      (node (ref "U$3") (pin "MISO") (pinfunction "MISO_MISO") (pintype "bidirectional"))
    )
    (net (code "62") (name "/MOSI") (class "Default")
      (node (ref "U$2") (pin "D51") (pinfunction "51_D51") (pintype "bidirectional"))
      (node (ref "U$3") (pin "MOSI") (pinfunction "MOSI_MOSI") (pintype "bidirectional"))
    )
    (net (code "63") (name "/O0") (class "Default")
      (node (ref "IC5") (pin "2") (pinfunction "1D_2") (pintype "input"))
      (node (ref "U$2") (pin "A15") (pinfunction "A15_A15") (pintype "bidirectional"))
    )
    (net (code "64") (name "/O1") (class "Default")
      (node (ref "IC5") (pin "3") (pinfunction "2D_3") (pintype "input"))
      (node (ref "U$2") (pin "A14") (pinfunction "A14_A14") (pintype "bidirectional"))
    )
    (net (code "65") (name "/O2") (class "Default")
      (node (ref "IC5") (pin "4") (pinfunction "3D_4") (pintype "input"))
      (node (ref "U$2") (pin "A13") (pinfunction "A13_A13") (pintype "bidirectional"))
    )
    (net (code "66") (name "/O3") (class "Default")
      (node (ref "IC5") (pin "5") (pinfunction "4D_5") (pintype "input"))
      (node (ref "U$2") (pin "A12") (pinfunction "A12_A12") (pintype "bidirectional"))
    )
    (net (code "67") (name "/O4") (class "Default")
      (node (ref "IC5") (pin "6") (pinfunction "5D_6") (pintype "input"))
      (node (ref "U$2") (pin "A11") (pinfunction "A11_A11") (pintype "bidirectional"))
    )
    (net (code "68") (name "/O5") (class "Default")
      (node (ref "IC5") (pin "7") (pinfunction "6D_7") (pintype "input"))
      (node (ref "U$2") (pin "A10") (pinfunction "A10_A10") (pintype "bidirectional"))
    )
    (net (code "69") (name "/O6") (class "Default")
      (node (ref "IC5") (pin "8") (pinfunction "7D_8") (pintype "input"))
      (node (ref "U$2") (pin "A9") (pinfunction "A9_A9") (pintype "bidirectional"))
    )
    (net (code "70") (name "/O7") (class "Default")
      (node (ref "IC5") (pin "9") (pinfunction "8D_9") (pintype "input"))
      (node (ref "U$2") (pin "A8") (pinfunction "A8_A8") (pintype "bidirectional"))
    )
    (net (code "71") (name "/OE_OL") (class "Default")
      (node (ref "IC9") (pin "1") (pinfunction "OC_1") (pintype "input"))
      (node (ref "U$2") (pin "D16") (pinfunction "16(TX2)_D16") (pintype "bidirectional"))
    )
    (net (code "72") (name "/PAGE_A8") (class "Default")
      (node (ref "IC4") (pin "80") (pinfunction "FB6MC11_80") (pintype "bidirectional"))
      (node (ref "U$2") (pin "D43") (pinfunction "43_D43") (pintype "bidirectional"))
    )
    (net (code "73") (name "/ROM_WR_EN") (class "Default")
      (node (ref "IC4") (pin "79") (pinfunction "FB6MC9_79") (pintype "bidirectional"))
      (node (ref "U$2") (pin "D48") (pinfunction "48_D48") (pintype "bidirectional"))
    )
    (net (code "74") (name "/RST_CTRL_REG") (class "Default")
      (node (ref "IC4") (pin "82") (pinfunction "FB6MC14_82") (pintype "bidirectional"))
      (node (ref "U$2") (pin "D13") (pinfunction "13_D13") (pintype "bidirectional"))
    )
    (net (code "75") (name "/RST_DATA_REG") (class "Default")
      (node (ref "IC4") (pin "81") (pinfunction "FB6MC12_81") (pintype "bidirectional"))
      (node (ref "U$2") (pin "D15") (pinfunction "15(RX3)_D15") (pintype "bidirectional"))
    )
    (net (code "76") (name "/SCLK") (class "Default")
      (node (ref "U$2") (pin "D52") (pinfunction "52_D52") (pintype "bidirectional"))
      (node (ref "U$3") (pin "SCK") (pinfunction "SCK_SCK") (pintype "bidirectional"))
    )
    (net (code "77") (name "/SD_LED") (class "Default")
      (node (ref "LED1") (pin "K") (pinfunction "C_K") (pintype "passive"))
      (node (ref "U$2") (pin "D47") (pinfunction "47_D47") (pintype "bidirectional"))
    )
    (net (code "78") (name "/SEL_128CHARS") (class "Default")
      (node (ref "IC4") (pin "78") (pinfunction "FB6MC8_78") (pintype "bidirectional"))
      (node (ref "U$2") (pin "D49") (pinfunction "49_D49") (pintype "bidirectional"))
    )
    (net (code "79") (name "/SPARE1") (class "Default")
      (node (ref "IC4") (pin "77") (pinfunction "FB6MC6_77") (pintype "bidirectional"))
      (node (ref "U$2") (pin "D46") (pinfunction "46_D46") (pintype "bidirectional"))
    )
    (net (code "80") (name "/SS_SD") (class "Default")
      (node (ref "U$2") (pin "D53") (pinfunction "53_D53") (pintype "bidirectional"))
      (node (ref "U$3") (pin "CS") (pinfunction "CS_CS") (pintype "bidirectional"))
    )
    (net (code "81") (name "/TCK") (class "Default")
      (node (ref "IC4") (pin "48") (pinfunction "TCK_48") (pintype "passive"))
      (node (ref "JP3") (pin "1") (pinfunction "1_1") (pintype "passive"))
      (node (ref "R7") (pin "2") (pinfunction "2_2") (pintype "passive"))
      (node (ref "R8") (pin "2") (pinfunction "2_2") (pintype "passive"))
    )
    (net (code "82") (name "/TDI") (class "Default")
      (node (ref "IC4") (pin "45") (pinfunction "TDI_45") (pintype "passive"))
      (node (ref "JP3") (pin "3") (pinfunction "3_3") (pintype "passive"))
      (node (ref "R5") (pin "2") (pinfunction "2_2") (pintype "passive"))
      (node (ref "R9") (pin "2") (pinfunction "2_2") (pintype "passive"))
    )
    (net (code "83") (name "/TDO") (class "Default")
      (node (ref "IC4") (pin "83") (pinfunction "TDO_83") (pintype "passive"))
      (node (ref "JP3") (pin "2") (pinfunction "2_2") (pintype "passive"))
      (node (ref "R6") (pin "2") (pinfunction "2_2") (pintype "passive"))
    )
    (net (code "84") (name "/TMS") (class "Default")
      (node (ref "IC4") (pin "47") (pinfunction "TMS_47") (pintype "passive"))
      (node (ref "JP3") (pin "4") (pinfunction "4_4") (pintype "passive"))
      (node (ref "R10") (pin "2") (pinfunction "2_2") (pintype "passive"))
      (node (ref "R4") (pin "2") (pinfunction "2_2") (pintype "passive"))
    )
    (net (code "85") (name "/{slash}BUSAK") (class "Default")
      (node (ref "18A") (pin "1") (pinfunction "P_1") (pintype "passive"))
      (node (ref "IC4") (pin "54") (pinfunction "FB7MC8_54") (pintype "bidirectional"))
    )
    (net (code "86") (name "/{slash}BUSRQ") (class "Default")
      (node (ref "20A") (pin "1") (pinfunction "P_1") (pintype "passive"))
      (node (ref "IC4") (pin "59") (pinfunction "FB7MC14_59") (pintype "bidirectional"))
    )
    (net (code "87") (name "/{slash}CLOCK") (class "Default")
      (node (ref "6B") (pin "1") (pinfunction "P_1") (pintype "passive"))
      (node (ref "IC4") (pin "22") (pinfunction "GCK1_22") (pintype "bidirectional"))
    )
    (net (code "88") (name "/{slash}HALT") (class "Default")
      (node (ref "13A") (pin "1") (pinfunction "P_1") (pintype "passive"))
      (node (ref "IC4") (pin "39") (pinfunction "FB5MC8_39") (pintype "bidirectional"))
    )
    (net (code "89") (name "/{slash}IORQ") (class "Default")
      (node (ref "15A") (pin "1") (pinfunction "P_1") (pintype "passive"))
      (node (ref "IC4") (pin "43") (pinfunction "FB5MC14_43") (pintype "bidirectional"))
    )
    (net (code "90") (name "/{slash}M1") (class "Default")
      (node (ref "22A") (pin "1") (pinfunction "P_1") (pintype "passive"))
      (node (ref "IC4") (pin "61") (pinfunction "FB7MC17_61") (pintype "bidirectional"))
    )
    (net (code "91") (name "/{slash}MEM_CE") (class "Default")
      (node (ref "IC1") (pin "22") (pinfunction "CE#_22") (pintype "input"))
      (node (ref "IC4") (pin "97") (pinfunction "FB4MC17_97") (pintype "bidirectional"))
      (node (ref "U$2") (pin "D38") (pinfunction "38_D38") (pintype "bidirectional"))
    )
    (net (code "92") (name "/{slash}MEM_OE") (class "Default")
      (node (ref "IC1") (pin "24") (pinfunction "OE#_24") (pintype "input"))
      (node (ref "IC4") (pin "12") (pinfunction "FB1MC3_12") (pintype "bidirectional"))
      (node (ref "U$2") (pin "D40") (pinfunction "40_D40") (pintype "bidirectional"))
    )
    (net (code "93") (name "/{slash}MREQ") (class "Default")
      (node (ref "14A") (pin "1") (pinfunction "P_1") (pintype "passive"))
      (node (ref "IC4") (pin "41") (pinfunction "FB5MC11_41") (pintype "bidirectional"))
    )
    (net (code "94") (name "/{slash}NMI") (class "Default")
      (node (ref "12A") (pin "1") (pinfunction "P_1") (pintype "passive"))
      (node (ref "IC4") (pin "36") (pinfunction "FB5MC5_36") (pintype "bidirectional"))
    )
    (net (code "95") (name "/{slash}OE_CTRL_CLOCK") (class "Default")
      (node (ref "IC3") (pin "10") (pinfunction "OE_10") (pintype "input"))
      (node (ref "IC4") (pin "10") (pinfunction "FB2MC17_10") (pintype "bidirectional"))
    )
    (net (code "96") (name "/{slash}OE_IL") (class "Default")
      (node (ref "IC4") (pin "15") (pinfunction "FB1MC8_15") (pintype "bidirectional"))
      (node (ref "IC5") (pin "1") (pinfunction "OC_1") (pintype "input"))
    )
    (net (code "97") (name "/{slash}OE_RAMCS") (class "Default")
      (node (ref "IC3") (pin "4") (pinfunction "OE_4") (pintype "input"))
      (node (ref "IC4") (pin "17") (pinfunction "FB1MC11_17") (pintype "bidirectional"))
    )
    (net (code "98") (name "/{slash}OE_ROMCS") (class "Default")
      (node (ref "IC3") (pin "1") (pinfunction "OE_1") (pintype "input"))
      (node (ref "IC4") (pin "14") (pinfunction "FB1MC6_14") (pintype "bidirectional"))
    )
    (net (code "99") (name "/{slash}RAMCS") (class "Default")
      (node (ref "2A") (pin "1") (pinfunction "P_1") (pintype "passive"))
      (node (ref "IC3") (pin "6") (pinfunction "O_6") (pintype "tri_state"))
    )
    (net (code "100") (name "/{slash}RD") (class "Default")
      (node (ref "16A") (pin "1") (pinfunction "P_1") (pintype "passive"))
      (node (ref "IC4") (pin "49") (pinfunction "FB5MC17_49") (pintype "bidirectional"))
    )
    (net (code "101") (name "/{slash}RESET") (class "Default")
      (node (ref "21A") (pin "1") (pinfunction "P_1") (pintype "passive"))
      (node (ref "IC4") (pin "71") (pinfunction "FB8MC14_71") (pintype "bidirectional"))
      (node (ref "U$2") (pin "D6") (pinfunction "6_D6") (pintype "bidirectional"))
    )
    (net (code "102") (name "/{slash}RFSH") (class "Default")
      (node (ref "23A") (pin "1") (pinfunction "P_1") (pintype "passive"))
      (node (ref "IC4") (pin "64") (pinfunction "FB8MC5_64") (pintype "bidirectional"))
    )
    (net (code "103") (name "/{slash}ROMCS") (class "Default")
      (node (ref "23B") (pin "1") (pinfunction "P_1") (pintype "passive"))
      (node (ref "IC3") (pin "3") (pinfunction "O_3") (pintype "tri_state"))
    )
    (net (code "104") (name "/{slash}WAIT") (class "Default")
      (node (ref "19A") (pin "1") (pinfunction "P_1") (pintype "passive"))
      (node (ref "IC4") (pin "56") (pinfunction "FB7MC11_56") (pintype "bidirectional"))
      (node (ref "U$2") (pin "D42") (pinfunction "42_D42") (pintype "bidirectional"))
    )
    (net (code "105") (name "/{slash}WR") (class "Default")
      (node (ref "17A") (pin "1") (pinfunction "P_1") (pintype "passive"))
      (node (ref "IC4") (pin "52") (pinfunction "FB7MC5_52") (pintype "bidirectional"))
    )
    (net (code "106") (name "/{slash}WR'") (class "Default")
      (node (ref "IC1") (pin "29") (pinfunction "WE#_29") (pintype "input"))
      (node (ref "IC4") (pin "13") (pinfunction "FB1MC5_13") (pintype "bidirectional"))
      (node (ref "U$2") (pin "D41") (pinfunction "41_D41") (pintype "bidirectional"))
    )
    (net (code "107") (name "GND") (class "Default")
      (node (ref "4B") (pin "1") (pinfunction "P_1") (pintype "passive"))
      (node (ref "5B") (pin "1") (pinfunction "P_1") (pintype "passive"))
      (node (ref "C1") (pin "2") (pinfunction "2_2") (pintype "passive"))
      (node (ref "C12") (pin "2") (pinfunction "2_2") (pintype "passive"))
      (node (ref "C2") (pin "2") (pinfunction "2_2") (pintype "passive"))
      (node (ref "C3") (pin "2") (pinfunction "2_2") (pintype "passive"))
      (node (ref "C8") (pin "-") (pinfunction "-_-") (pintype "passive"))
      (node (ref "C9") (pin "-") (pinfunction "-_-") (pintype "passive"))
      (node (ref "IC1") (pin "16") (pinfunction "VSS_16") (pintype "power_in"))
      (node (ref "IC2") (pin "1") (pinfunction "GND_1") (pintype "power_in"))
      (node (ref "IC4") (pin "100") (pinfunction "GND8_100") (pintype "power_in"))
      (node (ref "IC4") (pin "21") (pinfunction "GND1_21") (pintype "power_in"))
      (node (ref "IC4") (pin "31") (pinfunction "GND2_31") (pintype "power_in"))
      (node (ref "IC4") (pin "44") (pinfunction "GND3_44") (pintype "power_in"))
      (node (ref "IC4") (pin "62") (pinfunction "GND4_62") (pintype "power_in"))
      (node (ref "IC4") (pin "69") (pinfunction "GND5_69") (pintype "power_in"))
      (node (ref "IC4") (pin "75") (pinfunction "GND6_75") (pintype "power_in"))
      (node (ref "IC4") (pin "84") (pinfunction "GND7_84") (pintype "power_in"))
      (node (ref "IC7") (pin "2") (pinfunction "-IN_2") (pintype "input"))
      (node (ref "IC7") (pin "4") (pinfunction "GND_4") (pintype "power_in"))
      (node (ref "J1") (pin "SLEEVE") (pinfunction "SLEEVE_SLEEVE") (pintype "bidirectional"))
      (node (ref "JP2") (pin "2") (pinfunction "2_2") (pintype "passive"))
      (node (ref "LED2") (pin "2") (pinfunction "C_2") (pintype "bidirectional"))
      (node (ref "R1") (pin "P$1") (pinfunction "A_P$1") (pintype "passive"))
      (node (ref "R10") (pin "1") (pinfunction "1_1") (pintype "passive"))
      (node (ref "R16") (pin "1") (pinfunction "1_1") (pintype "passive"))
      (node (ref "R8") (pin "1") (pinfunction "1_1") (pintype "passive"))
      (node (ref "R9") (pin "1") (pinfunction "1_1") (pintype "passive"))
      (node (ref "S1") (pin "1") (pinfunction "S_1") (pintype "passive"))
      (node (ref "S1") (pin "2") (pinfunction "S1_2") (pintype "passive"))
      (node (ref "SP1") (pin "+") (pinfunction "1_+") (pintype "passive"))
      (node (ref "U$2") (pin "GND1") (pinfunction "GND._GND1") (pintype "bidirectional"))
      (node (ref "U$2") (pin "GND2") (pinfunction "GND.._GND2") (pintype "bidirectional"))
      (node (ref "U$3") (pin "GND") (pinfunction "GND.1_GND") (pintype "power_in"))
    )
    (net (code "108") (name "Net-(C7-Pad+)") (class "Default")
      (node (ref "C7") (pin "+") (pinfunction "+_+") (pintype "passive"))
      (node (ref "IC7") (pin "1") (pinfunction "GAIN_1") (pintype "passive"))
    )
    (net (code "109") (name "Net-(C7-Pad-)") (class "Default")
      (node (ref "C7") (pin "-") (pinfunction "-_-") (pintype "passive"))
      (node (ref "IC7") (pin "8") (pinfunction "GAIN_8") (pintype "passive"))
    )
    (net (code "110") (name "Net-(C10-Pad-)") (class "Default")
      (node (ref "C10") (pin "-") (pinfunction "-_-") (pintype "passive"))
      (node (ref "J1") (pin "RING") (pinfunction "RING_RING") (pintype "bidirectional"))
      (node (ref "J1") (pin "TIP") (pinfunction "TIP_TIP") (pintype "bidirectional"))
    )
    (net (code "111") (name "Net-(C11-Pad2)") (class "Default")
      (node (ref "C11") (pin "2") (pinfunction "2_2") (pintype "passive"))
      (node (ref "R16") (pin "2") (pinfunction "2_2") (pintype "passive"))
    )
    (net (code "112") (name "Net-(IC1-A17)") (class "Default")
      (node (ref "IC1") (pin "30") (pinfunction "A17_30") (pintype "input"))
      (node (ref "JP1") (pin "2") (pinfunction "2_2") (pintype "passive"))
    )
    (net (code "113") (name "Net-(IC4-FB6MC2)") (class "Default")
      (node (ref "IC4") (pin "74") (pinfunction "FB6MC2_74") (pintype "bidirectional"))
      (node (ref "PAD8") (pin "1") (pinfunction "P_1") (pintype "passive"))
    )
    (net (code "114") (name "Net-(IC4-FB8MC6)") (class "Default")
      (node (ref "IC4") (pin "65") (pinfunction "FB8MC6_65") (pintype "bidirectional"))
      (node (ref "PAD2") (pin "1") (pinfunction "P_1") (pintype "passive"))
    )
    (net (code "115") (name "Net-(IC4-FB8MC8)") (class "Default")
      (node (ref "IC4") (pin "66") (pinfunction "FB8MC8_66") (pintype "bidirectional"))
      (node (ref "PAD3") (pin "1") (pinfunction "P_1") (pintype "passive"))
    )
    (net (code "116") (name "Net-(IC4-FB8MC9)") (class "Default")
      (node (ref "IC4") (pin "67") (pinfunction "FB8MC9_67") (pintype "bidirectional"))
      (node (ref "PAD4") (pin "1") (pinfunction "P_1") (pintype "passive"))
    )
    (net (code "117") (name "Net-(IC4-FB8MC11)") (class "Default")
      (node (ref "IC4") (pin "68") (pinfunction "FB8MC11_68") (pintype "bidirectional"))
      (node (ref "PAD5") (pin "1") (pinfunction "P_1") (pintype "passive"))
    )
    (net (code "118") (name "Net-(IC4-FB8MC12)") (class "Default")
      (node (ref "IC4") (pin "70") (pinfunction "FB8MC12_70") (pintype "bidirectional"))
      (node (ref "PAD7") (pin "1") (pinfunction "P_1") (pintype "passive"))
    )
    (net (code "119") (name "Net-(IC4-FB8MC17)") (class "Default")
      (node (ref "IC4") (pin "73") (pinfunction "FB8MC17_73") (pintype "bidirectional"))
      (node (ref "PAD6") (pin "1") (pinfunction "P_1") (pintype "passive"))
    )
    (net (code "120") (name "Net-(IC4-GCK3)") (class "Default")
      (node (ref "IC4") (pin "27") (pinfunction "GCK3_27") (pintype "bidirectional"))
      (node (ref "PAD1") (pin "1") (pinfunction "P_1") (pintype "passive"))
    )
    (net (code "121") (name "Net-(IC7-+IN)") (class "Default")
      (node (ref "IC7") (pin "3") (pinfunction "+IN_3") (pintype "input"))
      (node (ref "R1") (pin "P$3") (pinfunction "S_P$3") (pintype "passive"))
    )
    (net (code "122") (name "Net-(IC7-BYPASS)") (class "Default")
      (node (ref "C12") (pin "1") (pinfunction "1_1") (pintype "passive"))
      (node (ref "IC7") (pin "7") (pinfunction "BYPASS_7") (pintype "passive"))
    )
    (net (code "123") (name "Net-(IC7-OUT)") (class "Default")
      (node (ref "C10") (pin "+") (pinfunction "+_+") (pintype "passive"))
      (node (ref "C11") (pin "1") (pinfunction "1_1") (pintype "passive"))
      (node (ref "IC7") (pin "5") (pinfunction "OUT_5") (pintype "output"))
    )
    (net (code "124") (name "Net-(IC8A-OC)") (class "Default")
      (node (ref "IC8") (pin "1") (pinfunction "OC_1") (pintype "input"))
      (node (ref "U$2") (pin "D7") (pinfunction "7_D7") (pintype "bidirectional"))
    )
    (net (code "125") (name "Net-(LED1-PadA)") (class "Default")
      (node (ref "LED1") (pin "A") (pinfunction "A_A") (pintype "passive"))
      (node (ref "R11") (pin "2") (pinfunction "2_2") (pintype "passive"))
    )
    (net (code "126") (name "Net-(LED2-BLU)") (class "Default")
      (node (ref "LED2") (pin "3") (pinfunction "BLU_3") (pintype "bidirectional"))
      (node (ref "R13") (pin "2") (pinfunction "2_2") (pintype "passive"))
    )
    (net (code "127") (name "Net-(LED2-GRN)") (class "Default")
      (node (ref "LED2") (pin "4") (pinfunction "GRN_4") (pintype "bidirectional"))
      (node (ref "R3") (pin "2") (pinfunction "2_2") (pintype "passive"))
    )
    (net (code "128") (name "Net-(LED2-RED)") (class "Default")
      (node (ref "LED2") (pin "1") (pinfunction "RED_1") (pintype "bidirectional"))
      (node (ref "R2") (pin "2") (pinfunction "2_2") (pintype "passive"))
    )
    (net (code "129") (name "Net-(R1-E)") (class "Default")
      (node (ref "R1") (pin "P$2") (pinfunction "E_P$2") (pintype "passive"))
      (node (ref "R12") (pin "2") (pinfunction "2_2") (pintype "passive"))
    )
    (net (code "130") (name "Net-(S1-P)") (class "Default")
      (node (ref "S1") (pin "3") (pinfunction "P_3") (pintype "passive"))
      (node (ref "S1") (pin "4") (pinfunction "P1_4") (pintype "passive"))
      (node (ref "U$2") (pin "RESET.") (pinfunction "RESET_RESET.") (pintype "bidirectional"))
    )
    (net (code "131") (name "Net-(SP1-2)") (class "Default")
      (node (ref "J1") (pin "RSH") (pinfunction "RSH_RSH") (pintype "bidirectional"))
      (node (ref "J1") (pin "TSH") (pinfunction "TSH_TSH") (pintype "bidirectional"))
      (node (ref "SP1") (pin "-") (pinfunction "2_-") (pintype "passive"))
    )
    (net (code "132") (name "Net-(U$2-2)") (class "Default")
      (node (ref "R2") (pin "1") (pinfunction "1_1") (pintype "passive"))
      (node (ref "U$2") (pin "D2") (pinfunction "2_D2") (pintype "bidirectional"))
    )
    (net (code "133") (name "Net-(U$2-3)") (class "Default")
      (node (ref "R3") (pin "1") (pinfunction "1_1") (pintype "passive"))
      (node (ref "U$2") (pin "D3") (pinfunction "3_D3") (pintype "bidirectional"))
    )
    (net (code "134") (name "Net-(U$2-4)") (class "Default")
      (node (ref "R13") (pin "1") (pinfunction "1_1") (pintype "passive"))
      (node (ref "U$2") (pin "D4") (pinfunction "4_D4") (pintype "bidirectional"))
    )
    (net (code "135") (name "Net-(U$2-8)") (class "Default")
      (node (ref "R4") (pin "1") (pinfunction "1_1") (pintype "passive"))
      (node (ref "U$2") (pin "D8") (pinfunction "8_D8") (pintype "bidirectional"))
    )
    (net (code "136") (name "Net-(U$2-9)") (class "Default")
      (node (ref "R5") (pin "1") (pinfunction "1_1") (pintype "passive"))
      (node (ref "U$2") (pin "D9") (pinfunction "9_D9") (pintype "bidirectional"))
    )
    (net (code "137") (name "Net-(U$2-10)") (class "Default")
      (node (ref "R6") (pin "1") (pinfunction "1_1") (pintype "passive"))
      (node (ref "U$2") (pin "D10") (pinfunction "10_D10") (pintype "bidirectional"))
    )
    (net (code "138") (name "Net-(U$2-11)") (class "Default")
      (node (ref "R7") (pin "1") (pinfunction "1_1") (pintype "passive"))
      (node (ref "U$2") (pin "D11") (pinfunction "11_D11") (pintype "bidirectional"))
    )
    (net (code "139") (name "Net-(U$2-45)") (class "Default")
      (node (ref "R12") (pin "1") (pinfunction "1_1") (pintype "passive"))
      (node (ref "U$2") (pin "D45") (pinfunction "45_D45") (pintype "bidirectional"))
    )
    (net (code "140") (name "VCC") (class "Default")
      (node (ref "1B") (pin "1") (pinfunction "P_1") (pintype "passive"))
      (node (ref "C2") (pin "1") (pinfunction "1_1") (pintype "passive"))
      (node (ref "C3") (pin "1") (pinfunction "1_1") (pintype "passive"))
      (node (ref "C8") (pin "+") (pinfunction "+_+") (pintype "passive"))
      (node (ref "IC1") (pin "32") (pinfunction "VCC_32") (pintype "power_in"))
      (node (ref "IC2") (pin "3") (pinfunction "VIN_3") (pintype "input"))
      (node (ref "IC3") (pin "12") (pinfunction "I_12") (pintype "input"))
      (node (ref "IC3") (pin "13") (pinfunction "OE_13") (pintype "input"))
      (node (ref "IC3") (pin "2") (pinfunction "I_2") (pintype "input"))
      (node (ref "IC3") (pin "5") (pinfunction "I_5") (pintype "input"))
      (node (ref "JP1") (pin "1") (pinfunction "1_1") (pintype "passive"))
      (node (ref "R11") (pin "1") (pinfunction "1_1") (pintype "passive"))
      (node (ref "U$2") (pin "5V1") (pinfunction "5V_5V1") (pintype "bidirectional"))
      (node (ref "U$2") (pin "5V2") (pinfunction "5V.._5V2") (pintype "bidirectional"))
      (node (ref "U$3") (pin "VCC") (pinfunction "5V_VCC") (pintype "power_in"))
    )
    (net (code "141") (name "unconnected-(IC3D-O-Pad11)") (class "Default")
      (node (ref "IC3") (pin "11") (pinfunction "O_11") (pintype "tri_state"))
    )
    (net (code "142") (name "unconnected-(U$2-0(RX)-PadRX)") (class "Default")
      (node (ref "U$2") (pin "RX") (pinfunction "0(RX)_RX") (pintype "bidirectional"))
    )
    (net (code "143") (name "unconnected-(U$2-1(TX)-PadTX)") (class "Default")
      (node (ref "U$2") (pin "TX") (pinfunction "1(TX)_TX") (pintype "bidirectional"))
    )
    (net (code "144") (name "unconnected-(U$2-Pad+5V_)") (class "Default")
      (node (ref "U$2") (pin "+5V_") (pinfunction "+5V__+5V_") (pintype "bidirectional"))
    )
    (net (code "145") (name "unconnected-(U$2-PadAREF)") (class "Default")
      (node (ref "U$2") (pin "AREF") (pinfunction "AREF_AREF") (pintype "bidirectional"))
    )
    (net (code "146") (name "unconnected-(U$2-PadGND__)") (class "Default")
      (node (ref "U$2") (pin "GND__") (pinfunction "GND___GND__") (pintype "bidirectional"))
    )
    (net (code "147") (name "unconnected-(U$2-PadMISO)") (class "Default")
      (node (ref "U$2") (pin "MISO") (pinfunction "MISO_MISO") (pintype "bidirectional"))
    )
    (net (code "148") (name "unconnected-(U$2-PadMOSI)") (class "Default")
      (node (ref "U$2") (pin "MOSI") (pinfunction "MOSI_MOSI") (pintype "bidirectional"))
    )
    (net (code "149") (name "unconnected-(U$2-PadSCK)") (class "Default")
      (node (ref "U$2") (pin "SCK") (pinfunction "SCK_SCK") (pintype "bidirectional"))
    )
    (net (code "150") (name "unconnected-(U$2-RESET.-PadRST)") (class "Default")
      (node (ref "U$2") (pin "RST") (pinfunction "RESET._RST") (pintype "bidirectional"))
    )
    (net (code "151") (name "unconnected-(U$2-VIN-PadVIN1)") (class "Default")
      (node (ref "U$2") (pin "VIN1") (pinfunction "VIN_VIN1") (pintype "bidirectional"))
    )
    (net (code "152") (name "unconnected-(U$2-VIN..-PadVIN2)") (class "Default")
      (node (ref "U$2") (pin "VIN2") (pinfunction "VIN.._VIN2") (pintype "bidirectional"))
    )
  )
)
